# upper_meter.net
KiCad netlist of a schematic drawn in EAGLE
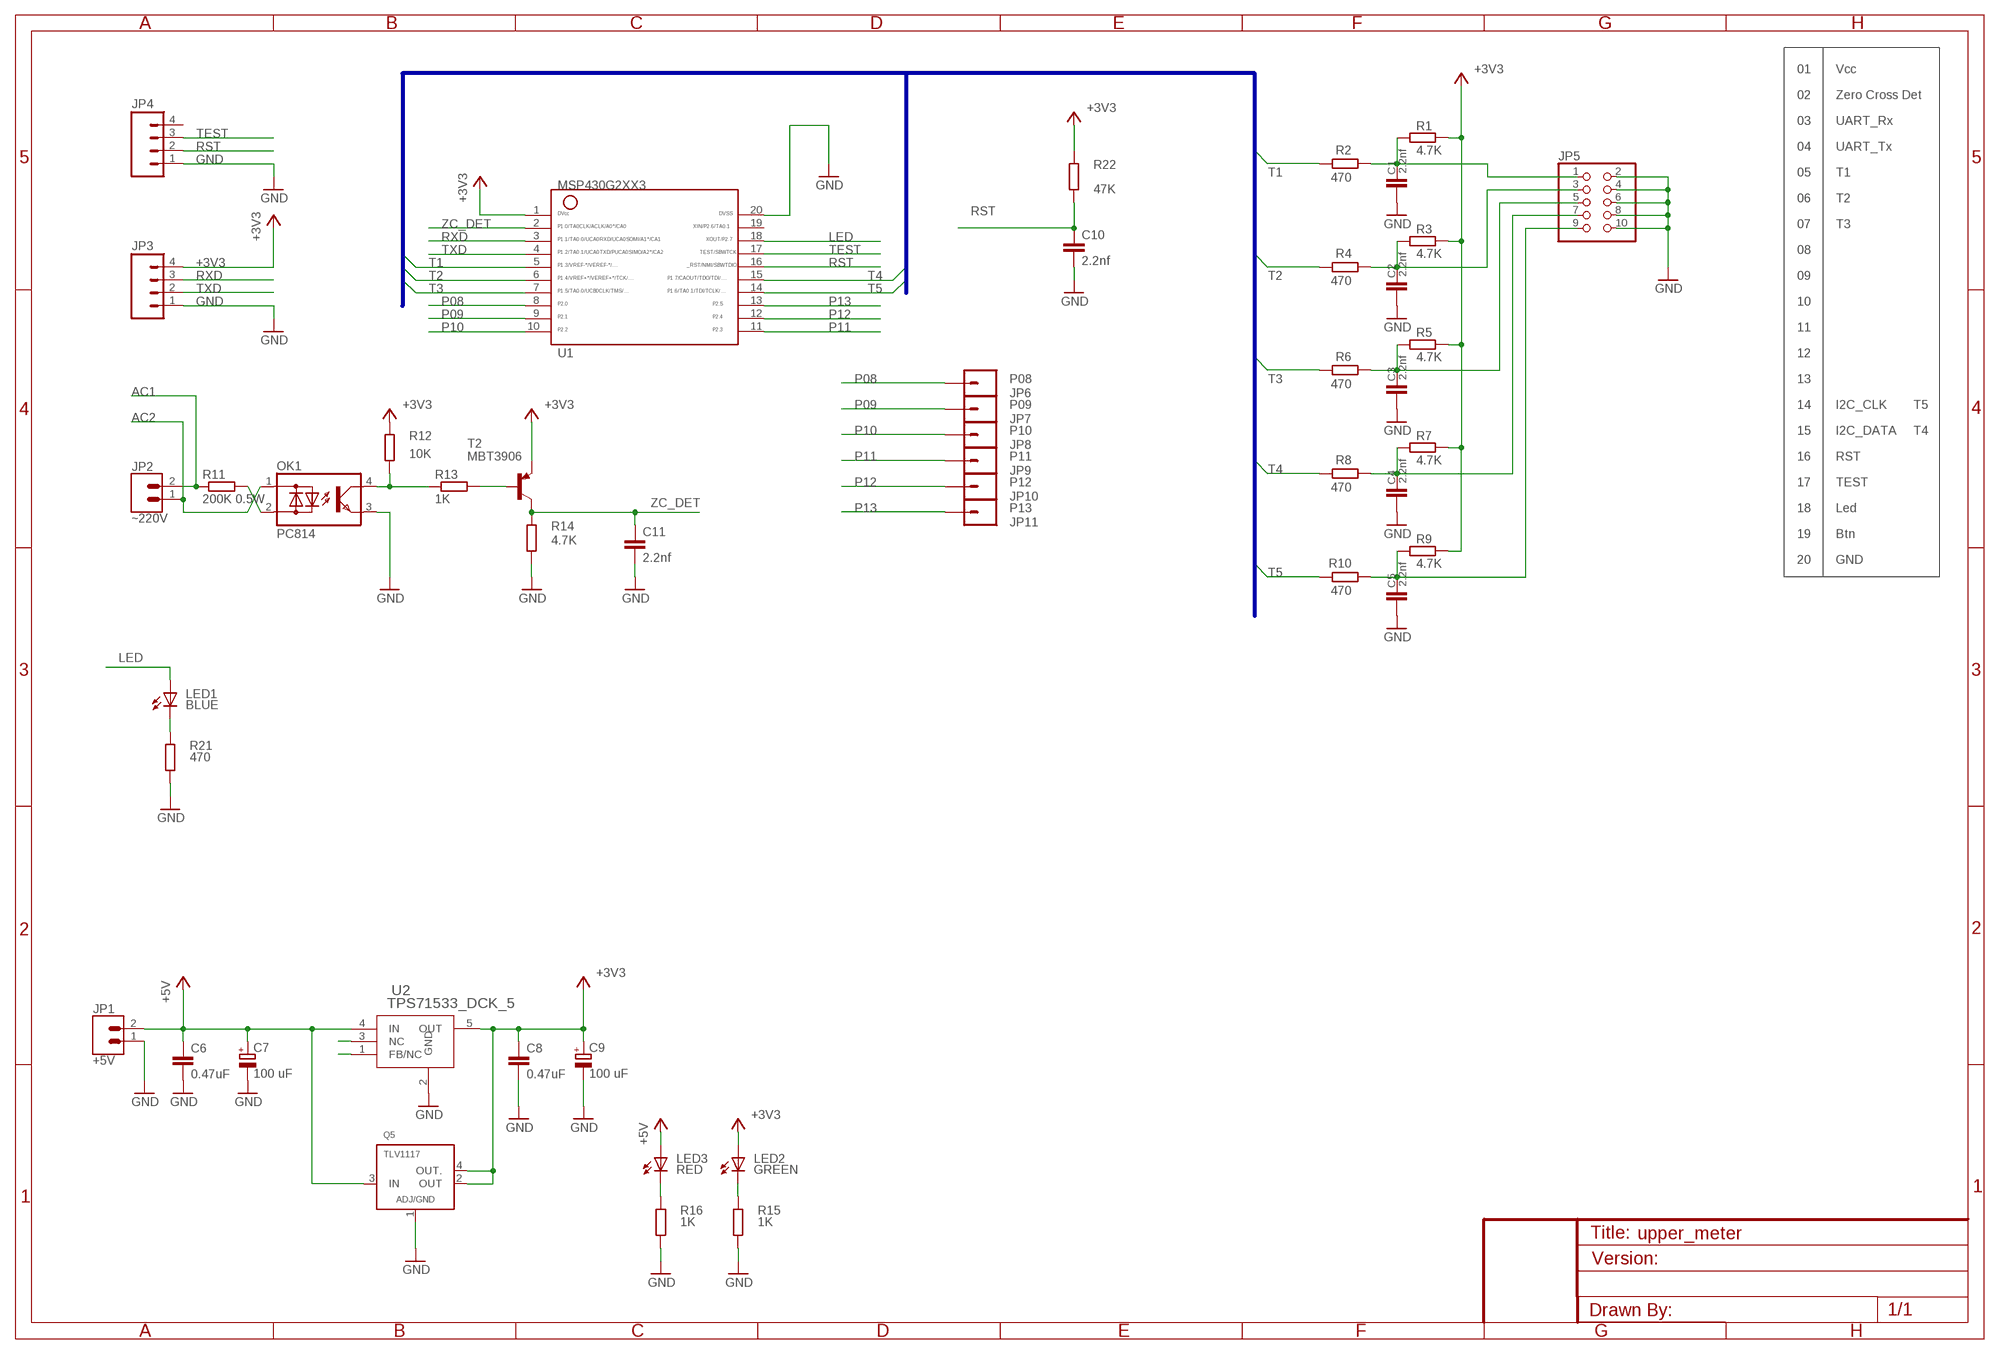
[diagram p0: schematic, sheet 1]

(export (version "E")
  (design (tool "Eeschema 10.0.6"))
  (components
    (comp (ref "C1")
      (value "2.2nf")
      (footprint "eagle-import:C0805")
      (libsource (lib "eagle-import") (part "C-EUC0805"))
    )
    (comp (ref "C2")
      (value "2.2nf")
      (footprint "eagle-import:C0805")
      (libsource (lib "eagle-import") (part "C-EUC0805"))
    )
    (comp (ref "C3")
      (value "2.2nf")
      (footprint "eagle-import:C0805")
      (libsource (lib "eagle-import") (part "C-EUC0805"))
    )
    (comp (ref "C4")
      (value "2.2nf")
      (footprint "eagle-import:C0805")
      (libsource (lib "eagle-import") (part "C-EUC0805"))
    )
    (comp (ref "C5")
      (value "2.2nf")
      (footprint "eagle-import:C0805")
      (libsource (lib "eagle-import") (part "resistor_C-EUC0805"))
    )
    (comp (ref "C6")
      (value "0.47uF")
      (footprint "eagle-import:C0805")
      (libsource (lib "eagle-import") (part "C-EUC0805"))
    )
    (comp (ref "C7")
      (value "100 uF")
      (footprint "eagle-import:E2,5-7")
      (libsource (lib "eagle-import") (part "CPOL-EUE2.5-7"))
    )
    (comp (ref "C8")
      (value "0.47uF")
      (footprint "eagle-import:C0805")
      (libsource (lib "eagle-import") (part "C-EUC0805"))
    )
    (comp (ref "C9")
      (value "100 uF")
      (footprint "eagle-import:E2,5-7")
      (libsource (lib "eagle-import") (part "CPOL-EUE2.5-7"))
    )
    (comp (ref "C10")
      (value "2.2nf")
      (footprint "eagle-import:C0805")
      (libsource (lib "eagle-import") (part "C-EUC0805"))
    )
    (comp (ref "C11")
      (value "2.2nf")
      (footprint "eagle-import:C0805")
      (libsource (lib "eagle-import") (part "C-EUC0805"))
    )
    (comp (ref "JP1")
      (value "+5V")
      (footprint "eagle-import:BLUE_TERM")
      (libsource (lib "eagle-import") (part "BLUE_TERM"))
    )
    (comp (ref "JP2")
      (value "~220V")
      (footprint "eagle-import:BLUE_TERM")
      (libsource (lib "eagle-import") (part "BLUE_TERM"))
    )
    (comp (ref "JP3")
      (value "M04PTH")
      (footprint "eagle-import:1X04")
      (libsource (lib "eagle-import") (part "M04PTH"))
    )
    (comp (ref "JP4")
      (value "M04PTH")
      (footprint "eagle-import:1X04")
      (libsource (lib "eagle-import") (part "M04PTH"))
    )
    (comp (ref "JP5")
      (value "PINHD-2X5")
      (footprint "eagle-import:2X05")
      (libsource (lib "eagle-import") (part "PINHD-2X5"))
    )
    (comp (ref "JP6")
      (value "P08")
      (footprint "eagle-import:1X01")
      (libsource (lib "eagle-import") (part "M01PTH"))
    )
    (comp (ref "JP7")
      (value "P09")
      (footprint "eagle-import:1X01")
      (libsource (lib "eagle-import") (part "M01PTH"))
    )
    (comp (ref "JP8")
      (value "P10")
      (footprint "eagle-import:1X01")
      (libsource (lib "eagle-import") (part "M01PTH"))
    )
    (comp (ref "JP9")
      (value "P11")
      (footprint "eagle-import:1X01")
      (libsource (lib "eagle-import") (part "M01PTH"))
    )
    (comp (ref "JP10")
      (value "P12")
      (footprint "eagle-import:1X01")
      (libsource (lib "eagle-import") (part "M01PTH"))
    )
    (comp (ref "JP11")
      (value "P13")
      (footprint "eagle-import:1X01")
      (libsource (lib "eagle-import") (part "M01PTH"))
    )
    (comp (ref "LED1")
      (value "BLUE")
      (footprint "eagle-import:CHIP-LED0805")
      (libsource (lib "eagle-import") (part "LEDCHIP-LED0805"))
    )
    (comp (ref "LED2")
      (value "GREEN")
      (footprint "eagle-import:CHIP-LED0805")
      (libsource (lib "eagle-import") (part "LEDCHIP-LED0805"))
    )
    (comp (ref "LED3")
      (value "RED")
      (footprint "eagle-import:CHIP-LED0805")
      (libsource (lib "eagle-import") (part "LEDCHIP-LED0805"))
    )
    (comp (ref "OK1")
      (value "PC814")
      (footprint "eagle-import:DIL04")
      (libsource (lib "eagle-import") (part "PC814"))
    )
    (comp (ref "Q5")
      (value "TLV1117")
      (footprint "eagle-import:SOT223-4")
      (libsource (lib "eagle-import") (part "TLV1117"))
    )
    (comp (ref "R1")
      (value "4.7K")
      (footprint "eagle-import:R0805")
      (libsource (lib "eagle-import") (part "R-EU_R0805"))
    )
    (comp (ref "R2")
      (value "470")
      (footprint "eagle-import:R0805")
      (libsource (lib "eagle-import") (part "R-EU_R0805"))
    )
    (comp (ref "R3")
      (value "4.7K")
      (footprint "eagle-import:R0805")
      (libsource (lib "eagle-import") (part "R-EU_R0805"))
    )
    (comp (ref "R4")
      (value "470")
      (footprint "eagle-import:R0805")
      (libsource (lib "eagle-import") (part "R-EU_R0805"))
    )
    (comp (ref "R5")
      (value "4.7K")
      (footprint "eagle-import:R0805")
      (libsource (lib "eagle-import") (part "R-EU_R0805"))
    )
    (comp (ref "R6")
      (value "470")
      (footprint "eagle-import:R0805")
      (libsource (lib "eagle-import") (part "R-EU_R0805"))
    )
    (comp (ref "R7")
      (value "4.7K")
      (footprint "eagle-import:R0805")
      (libsource (lib "eagle-import") (part "R-EU_R0805"))
    )
    (comp (ref "R8")
      (value "470")
      (footprint "eagle-import:R0805")
      (libsource (lib "eagle-import") (part "R-EU_R0805"))
    )
    (comp (ref "R9")
      (value "4.7K")
      (footprint "eagle-import:R0805")
      (libsource (lib "eagle-import") (part "R-EU_R0805"))
    )
    (comp (ref "R10")
      (value "470")
      (footprint "eagle-import:R0805")
      (libsource (lib "eagle-import") (part "R-EU_R0805"))
    )
    (comp (ref "R11")
      (value "200K 0.5W")
      (footprint "eagle-import:0309_12")
      (libsource (lib "eagle-import") (part "R-EU_0309/12"))
    )
    (comp (ref "R12")
      (value "10K")
      (footprint "eagle-import:R0805")
      (libsource (lib "eagle-import") (part "R-EU_R0805"))
    )
    (comp (ref "R13")
      (value "1K")
      (footprint "eagle-import:R0805")
      (libsource (lib "eagle-import") (part "R-EU_R0805"))
    )
    (comp (ref "R14")
      (value "4.7K")
      (footprint "eagle-import:R0805")
      (libsource (lib "eagle-import") (part "R-EU_R0805"))
    )
    (comp (ref "R15")
      (value "1K")
      (footprint "eagle-import:R0805")
      (libsource (lib "eagle-import") (part "R-EU_R0805"))
    )
    (comp (ref "R16")
      (value "1K")
      (footprint "eagle-import:R0805")
      (libsource (lib "eagle-import") (part "R-EU_R0805"))
    )
    (comp (ref "R21")
      (value "470")
      (footprint "eagle-import:R0805")
      (libsource (lib "eagle-import") (part "R-EU_R0805"))
    )
    (comp (ref "R22")
      (value "47K")
      (footprint "eagle-import:R0805")
      (libsource (lib "eagle-import") (part "R-EU_R0805"))
    )
    (comp (ref "T2")
      (value "MBT3906")
      (footprint "eagle-import:SOT23-BEC")
      (libsource (lib "eagle-import") (part "-PNP-SOT23-BECMMBT3906LT1"))
    )
    (comp (ref "U1")
      (value "G2XX3---PW20")
      (footprint "eagle-import:PW20")
      (libsource (lib "eagle-import") (part "G2XX3---PW20"))
    )
    (comp (ref "U2")
      (value "TPS71533_DCK_5")
      (footprint "eagle-import:DCK5")
      (fields
        (field (name "GENERIC_PART_NUMBER") "TPS71533")
        (field (name "MANUFACTURER") "Texas Instruments")
        (field (name "MANUFACTURER_PART_NUMBER") "tps71533_dck_5")
      )
      (libsource (lib "eagle-import") (part "TPS71533_DCK_5"))
    )
  )
  (nets
    (net (code "1") (name "+3V3") (class "Default")
      (node (ref "C8") (pin "1") (pinfunction "1_1") (pintype "passive"))
      (node (ref "C9") (pin "+") (pinfunction "+_+") (pintype "passive"))
      (node (ref "JP3") (pin "4") (pinfunction "4_4") (pintype "passive"))
      (node (ref "LED2") (pin "A") (pinfunction "A_A") (pintype "passive"))
      (node (ref "Q5") (pin "2") (pinfunction "OUT_2") (pintype "power_in"))
      (node (ref "Q5") (pin "4") (pinfunction "OUT._4") (pintype "power_in"))
      (node (ref "R1") (pin "1") (pinfunction "1_1") (pintype "passive"))
      (node (ref "R12") (pin "2") (pinfunction "2_2") (pintype "passive"))
      (node (ref "R22") (pin "2") (pinfunction "2_2") (pintype "passive"))
      (node (ref "R3") (pin "1") (pinfunction "1_1") (pintype "passive"))
      (node (ref "R5") (pin "1") (pinfunction "1_1") (pintype "passive"))
      (node (ref "R7") (pin "1") (pinfunction "1_1") (pintype "passive"))
      (node (ref "R9") (pin "1") (pinfunction "1_1") (pintype "passive"))
      (node (ref "T2") (pin "E") (pinfunction "E_E") (pintype "passive"))
      (node (ref "U1") (pin "1") (pinfunction "1_1") (pintype "bidirectional"))
      (node (ref "U2") (pin "5") (pinfunction "OUT_5") (pintype "output"))
    )
    (net (code "2") (name "+5V") (class "Default")
      (node (ref "C6") (pin "1") (pinfunction "1_1") (pintype "passive"))
      (node (ref "C7") (pin "+") (pinfunction "+_+") (pintype "passive"))
      (node (ref "JP1") (pin "2") (pinfunction "2_2") (pintype "passive"))
      (node (ref "LED3") (pin "A") (pinfunction "A_A") (pintype "passive"))
      (node (ref "Q5") (pin "3") (pinfunction "IN_3") (pintype "power_in"))
      (node (ref "U2") (pin "4") (pinfunction "IN_4") (pintype "input"))
    )
    (net (code "3") (name "/AC1") (class "Default")
      (node (ref "JP2") (pin "2") (pinfunction "2_2") (pintype "passive"))
      (node (ref "R11") (pin "1") (pinfunction "1_1") (pintype "passive"))
    )
    (net (code "4") (name "/AC2") (class "Default")
      (node (ref "JP2") (pin "1") (pinfunction "1_1") (pintype "passive"))
      (node (ref "OK1") (pin "1") (pinfunction "AC1_1") (pintype "passive"))
    )
    (net (code "5") (name "/LED") (class "Default")
      (node (ref "LED1") (pin "A") (pinfunction "A_A") (pintype "passive"))
      (node (ref "U1") (pin "18") (pinfunction "18_18") (pintype "bidirectional"))
    )
    (net (code "6") (name "/P08") (class "Default")
      (node (ref "JP6") (pin "1") (pinfunction "1_1") (pintype "passive"))
      (node (ref "U1") (pin "8") (pinfunction "8_8") (pintype "bidirectional"))
    )
    (net (code "7") (name "/P09") (class "Default")
      (node (ref "JP7") (pin "1") (pinfunction "1_1") (pintype "passive"))
      (node (ref "U1") (pin "9") (pinfunction "9_9") (pintype "bidirectional"))
    )
    (net (code "8") (name "/P10") (class "Default")
      (node (ref "JP8") (pin "1") (pinfunction "1_1") (pintype "passive"))
      (node (ref "U1") (pin "10") (pinfunction "10_10") (pintype "bidirectional"))
    )
    (net (code "9") (name "/P11") (class "Default")
      (node (ref "JP9") (pin "1") (pinfunction "1_1") (pintype "passive"))
      (node (ref "U1") (pin "11") (pinfunction "11_11") (pintype "bidirectional"))
    )
    (net (code "10") (name "/P12") (class "Default")
      (node (ref "JP10") (pin "1") (pinfunction "1_1") (pintype "passive"))
      (node (ref "U1") (pin "12") (pinfunction "12_12") (pintype "bidirectional"))
    )
    (net (code "11") (name "/P13") (class "Default")
      (node (ref "JP11") (pin "1") (pinfunction "1_1") (pintype "passive"))
      (node (ref "U1") (pin "13") (pinfunction "13_13") (pintype "bidirectional"))
    )
    (net (code "12") (name "/RST") (class "Default")
      (node (ref "C10") (pin "1") (pinfunction "1_1") (pintype "passive"))
      (node (ref "JP4") (pin "2") (pinfunction "2_2") (pintype "passive"))
      (node (ref "R22") (pin "1") (pinfunction "1_1") (pintype "passive"))
      (node (ref "U1") (pin "16") (pinfunction "16_16") (pintype "bidirectional"))
    )
    (net (code "13") (name "/RXD") (class "Default")
      (node (ref "JP3") (pin "3") (pinfunction "3_3") (pintype "passive"))
      (node (ref "U1") (pin "3") (pinfunction "3_3") (pintype "bidirectional"))
    )
    (net (code "14") (name "/T1") (class "Default")
      (node (ref "R2") (pin "1") (pinfunction "1_1") (pintype "passive"))
      (node (ref "U1") (pin "5") (pinfunction "5_5") (pintype "bidirectional"))
    )
    (net (code "15") (name "/T2") (class "Default")
      (node (ref "R4") (pin "1") (pinfunction "1_1") (pintype "passive"))
      (node (ref "U1") (pin "6") (pinfunction "6_6") (pintype "bidirectional"))
    )
    (net (code "16") (name "/T3") (class "Default")
      (node (ref "R6") (pin "1") (pinfunction "1_1") (pintype "passive"))
      (node (ref "U1") (pin "7") (pinfunction "7_7") (pintype "bidirectional"))
    )
    (net (code "17") (name "/T4") (class "Default")
      (node (ref "R8") (pin "1") (pinfunction "1_1") (pintype "passive"))
      (node (ref "U1") (pin "15") (pinfunction "15_15") (pintype "bidirectional"))
    )
    (net (code "18") (name "/T5") (class "Default")
      (node (ref "R10") (pin "1") (pinfunction "1_1") (pintype "passive"))
      (node (ref "U1") (pin "14") (pinfunction "14_14") (pintype "bidirectional"))
    )
    (net (code "19") (name "/TEST") (class "Default")
      (node (ref "JP4") (pin "3") (pinfunction "3_3") (pintype "passive"))
      (node (ref "U1") (pin "17") (pinfunction "17_17") (pintype "bidirectional"))
    )
    (net (code "20") (name "/TXD") (class "Default")
      (node (ref "JP3") (pin "2") (pinfunction "2_2") (pintype "passive"))
      (node (ref "U1") (pin "4") (pinfunction "4_4") (pintype "bidirectional"))
    )
    (net (code "21") (name "/ZC_DET") (class "Default")
      (node (ref "C11") (pin "1") (pinfunction "1_1") (pintype "passive"))
      (node (ref "R14") (pin "2") (pinfunction "2_2") (pintype "passive"))
      (node (ref "T2") (pin "C") (pinfunction "C_C") (pintype "passive"))
      (node (ref "U1") (pin "2") (pinfunction "2_2") (pintype "bidirectional"))
    )
    (net (code "22") (name "GND") (class "Default")
      (node (ref "C1") (pin "1") (pinfunction "1_1") (pintype "passive"))
      (node (ref "C10") (pin "2") (pinfunction "2_2") (pintype "passive"))
      (node (ref "C11") (pin "2") (pinfunction "2_2") (pintype "passive"))
      (node (ref "C2") (pin "1") (pinfunction "1_1") (pintype "passive"))
      (node (ref "C3") (pin "1") (pinfunction "1_1") (pintype "passive"))
      (node (ref "C4") (pin "1") (pinfunction "1_1") (pintype "passive"))
      (node (ref "C5") (pin "1") (pinfunction "1_1") (pintype "passive"))
      (node (ref "C6") (pin "2") (pinfunction "2_2") (pintype "passive"))
      (node (ref "C7") (pin "-") (pinfunction "-_-") (pintype "passive"))
      (node (ref "C8") (pin "2") (pinfunction "2_2") (pintype "passive"))
      (node (ref "C9") (pin "-") (pinfunction "-_-") (pintype "passive"))
      (node (ref "JP1") (pin "1") (pinfunction "1_1") (pintype "passive"))
      (node (ref "JP3") (pin "1") (pinfunction "1_1") (pintype "passive"))
      (node (ref "JP4") (pin "1") (pinfunction "1_1") (pintype "passive"))
      (node (ref "JP5") (pin "10") (pinfunction "10_10") (pintype "passive"))
      (node (ref "JP5") (pin "2") (pinfunction "2_2") (pintype "passive"))
      (node (ref "JP5") (pin "4") (pinfunction "4_4") (pintype "passive"))
      (node (ref "JP5") (pin "6") (pinfunction "6_6") (pintype "passive"))
      (node (ref "JP5") (pin "8") (pinfunction "8_8") (pintype "passive"))
      (node (ref "OK1") (pin "3") (pinfunction "E_3") (pintype "passive"))
      (node (ref "Q5") (pin "1") (pinfunction "ADJ/GND_1") (pintype "bidirectional"))
      (node (ref "R14") (pin "1") (pinfunction "1_1") (pintype "passive"))
      (node (ref "R15") (pin "1") (pinfunction "1_1") (pintype "passive"))
      (node (ref "R16") (pin "1") (pinfunction "1_1") (pintype "passive"))
      (node (ref "R21") (pin "1") (pinfunction "1_1") (pintype "passive"))
      (node (ref "U1") (pin "20") (pinfunction "20_20") (pintype "bidirectional"))
      (node (ref "U2") (pin "2") (pinfunction "GND_2") (pintype "power_in"))
    )
    (net (code "23") (name "Net-(C1-Pad2)") (class "Default")
      (node (ref "C1") (pin "2") (pinfunction "2_2") (pintype "passive"))
      (node (ref "JP5") (pin "1") (pinfunction "1_1") (pintype "passive"))
      (node (ref "R1") (pin "2") (pinfunction "2_2") (pintype "passive"))
      (node (ref "R2") (pin "2") (pinfunction "2_2") (pintype "passive"))
    )
    (net (code "24") (name "Net-(C2-Pad2)") (class "Default")
      (node (ref "C2") (pin "2") (pinfunction "2_2") (pintype "passive"))
      (node (ref "JP5") (pin "3") (pinfunction "3_3") (pintype "passive"))
      (node (ref "R3") (pin "2") (pinfunction "2_2") (pintype "passive"))
      (node (ref "R4") (pin "2") (pinfunction "2_2") (pintype "passive"))
    )
    (net (code "25") (name "Net-(C3-Pad2)") (class "Default")
      (node (ref "C3") (pin "2") (pinfunction "2_2") (pintype "passive"))
      (node (ref "JP5") (pin "5") (pinfunction "5_5") (pintype "passive"))
      (node (ref "R5") (pin "2") (pinfunction "2_2") (pintype "passive"))
      (node (ref "R6") (pin "2") (pinfunction "2_2") (pintype "passive"))
    )
    (net (code "26") (name "Net-(C4-Pad2)") (class "Default")
      (node (ref "C4") (pin "2") (pinfunction "2_2") (pintype "passive"))
      (node (ref "JP5") (pin "7") (pinfunction "7_7") (pintype "passive"))
      (node (ref "R7") (pin "2") (pinfunction "2_2") (pintype "passive"))
      (node (ref "R8") (pin "2") (pinfunction "2_2") (pintype "passive"))
    )
    (net (code "27") (name "Net-(C5-Pad2)") (class "Default")
      (node (ref "C5") (pin "2") (pinfunction "2_2") (pintype "passive"))
      (node (ref "JP5") (pin "9") (pinfunction "9_9") (pintype "passive"))
      (node (ref "R10") (pin "2") (pinfunction "2_2") (pintype "passive"))
      (node (ref "R9") (pin "2") (pinfunction "2_2") (pintype "passive"))
    )
    (net (code "28") (name "Net-(LED1-PadC)") (class "Default")
      (node (ref "LED1") (pin "C") (pinfunction "C_C") (pintype "passive"))
      (node (ref "R21") (pin "2") (pinfunction "2_2") (pintype "passive"))
    )
    (net (code "29") (name "Net-(LED2-PadC)") (class "Default")
      (node (ref "LED2") (pin "C") (pinfunction "C_C") (pintype "passive"))
      (node (ref "R15") (pin "2") (pinfunction "2_2") (pintype "passive"))
    )
    (net (code "30") (name "Net-(LED3-PadC)") (class "Default")
      (node (ref "LED3") (pin "C") (pinfunction "C_C") (pintype "passive"))
      (node (ref "R16") (pin "2") (pinfunction "2_2") (pintype "passive"))
    )
    (net (code "31") (name "Net-(OK1-AC2)") (class "Default")
      (node (ref "OK1") (pin "2") (pinfunction "AC2_2") (pintype "passive"))
      (node (ref "R11") (pin "2") (pinfunction "2_2") (pintype "passive"))
    )
    (net (code "32") (name "Net-(OK1-C)") (class "Default")
      (node (ref "OK1") (pin "4") (pinfunction "C_4") (pintype "passive"))
      (node (ref "R12") (pin "1") (pinfunction "1_1") (pintype "passive"))
      (node (ref "R13") (pin "1") (pinfunction "1_1") (pintype "passive"))
    )
    (net (code "33") (name "Net-(R13-Pad2)") (class "Default")
      (node (ref "R13") (pin "2") (pinfunction "2_2") (pintype "passive"))
      (node (ref "T2") (pin "B") (pinfunction "B_B") (pintype "passive"))
    )
    (net (code "34") (name "unconnected-(JP4-Pad4)") (class "Default")
      (node (ref "JP4") (pin "4") (pinfunction "4_4") (pintype "passive"))
    )
    (net (code "35") (name "unconnected-(U1-Pad19)") (class "Default")
      (node (ref "U1") (pin "19") (pinfunction "19_19") (pintype "bidirectional"))
    )
    (net (code "36") (name "unconnected-(U2-FB{slash}NC-Pad1)") (class "Default")
      (node (ref "U2") (pin "1") (pinfunction "FB/NC_1") (pintype "bidirectional"))
    )
    (net (code "37") (name "unconnected-(U2-NC-Pad3)") (class "Default")
      (node (ref "U2") (pin "3") (pinfunction "NC_3") (pintype "passive"))
    )
  )
)
